# nomis.net
KiCad netlist of a schematic drawn in EAGLE
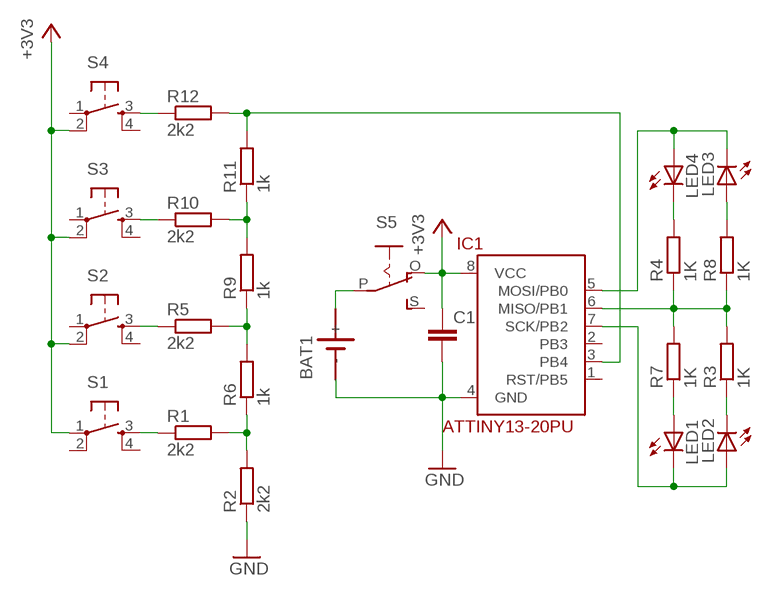
[diagram p0: schematic, sheet 1]

(export (version "E")
  (design (tool "Eeschema 10.0.6"))
  (components
    (comp (ref "BAT1")
      (value "SN2032")
      (footprint "eagle-import:SN2032")
      (libsource (lib "eagle-import") (part "SN2032"))
    )
    (comp (ref "C1")
      (value "C-EU025-025X050")
      (footprint "eagle-import:C025-025X050")
      (libsource (lib "eagle-import") (part "C-EU025-025X050"))
    )
    (comp (ref "IC1")
      (value "ATTINY13-20PU")
      (footprint "eagle-import:DIL08")
      (libsource (lib "eagle-import") (part "ATTINY13-20PU"))
    )
    (comp (ref "LED1")
      (value "LED5MM")
      (footprint "eagle-import:LED5MM")
      (libsource (lib "eagle-import") (part "LED5MM"))
    )
    (comp (ref "LED2")
      (value "LED5MM")
      (footprint "eagle-import:LED5MM")
      (libsource (lib "eagle-import") (part "LED5MM"))
    )
    (comp (ref "LED3")
      (value "LED5MM")
      (footprint "eagle-import:LED5MM")
      (libsource (lib "eagle-import") (part "LED5MM"))
    )
    (comp (ref "LED4")
      (value "LED5MM")
      (footprint "eagle-import:LED5MM")
      (libsource (lib "eagle-import") (part "LED5MM"))
    )
    (comp (ref "R1")
      (value "2k2")
      (footprint "eagle-import:0207_7")
      (libsource (lib "eagle-import") (part "R-EU_0207/7"))
    )
    (comp (ref "R2")
      (value "2k2")
      (footprint "eagle-import:0207_7")
      (libsource (lib "eagle-import") (part "R-EU_0207/7"))
    )
    (comp (ref "R3")
      (value "1K")
      (footprint "eagle-import:0207_7")
      (libsource (lib "eagle-import") (part "R-EU_0207/7"))
    )
    (comp (ref "R4")
      (value "1K")
      (footprint "eagle-import:0207_7")
      (libsource (lib "eagle-import") (part "R-EU_0207/7"))
    )
    (comp (ref "R5")
      (value "2k2")
      (footprint "eagle-import:0207_7")
      (libsource (lib "eagle-import") (part "R-EU_0207/7"))
    )
    (comp (ref "R6")
      (value "1k")
      (footprint "eagle-import:0207_7")
      (libsource (lib "eagle-import") (part "R-EU_0207/7"))
    )
    (comp (ref "R7")
      (value "1K")
      (footprint "eagle-import:0207_7")
      (libsource (lib "eagle-import") (part "R-EU_0207/7"))
    )
    (comp (ref "R8")
      (value "1K")
      (footprint "eagle-import:0207_7")
      (libsource (lib "eagle-import") (part "R-EU_0207/7"))
    )
    (comp (ref "R9")
      (value "1k")
      (footprint "eagle-import:0207_7")
      (libsource (lib "eagle-import") (part "R-EU_0207/7"))
    )
    (comp (ref "R10")
      (value "2k2")
      (footprint "eagle-import:0207_7")
      (libsource (lib "eagle-import") (part "R-EU_0207/7"))
    )
    (comp (ref "R11")
      (value "1k")
      (footprint "eagle-import:0207_7")
      (libsource (lib "eagle-import") (part "R-EU_0207/7"))
    )
    (comp (ref "R12")
      (value "2k2")
      (footprint "eagle-import:0207_7")
      (libsource (lib "eagle-import") (part "R-EU_0207/7"))
    )
    (comp (ref "S1")
      (value "TAC_SWITCHPTH")
      (footprint "eagle-import:TACTILE-PTH")
      (libsource (lib "eagle-import") (part "TAC_SWITCHPTH"))
    )
    (comp (ref "S2")
      (value "TAC_SWITCHPTH")
      (footprint "eagle-import:TACTILE-PTH")
      (libsource (lib "eagle-import") (part "TAC_SWITCHPTH"))
    )
    (comp (ref "S3")
      (value "TAC_SWITCHPTH")
      (footprint "eagle-import:TACTILE-PTH")
      (libsource (lib "eagle-import") (part "TAC_SWITCHPTH"))
    )
    (comp (ref "S4")
      (value "TAC_SWITCHPTH")
      (footprint "eagle-import:TACTILE-PTH")
      (libsource (lib "eagle-import") (part "TAC_SWITCHPTH"))
    )
    (comp (ref "S5")
      (value "EG1218S")
      (footprint "eagle-import:EG1218")
      (libsource (lib "eagle-import") (part "EG1218S"))
    )
  )
  (nets
    (net (code "1") (name "+3V3") (class "Default")
      (node (ref "C1") (pin "1") (pinfunction "1_1") (pintype "passive"))
      (node (ref "IC1") (pin "8") (pinfunction "VCC_8") (pintype "power_in"))
      (node (ref "S1") (pin "1") (pinfunction "1_1") (pintype "passive"))
      (node (ref "S2") (pin "2") (pinfunction "2_2") (pintype "passive"))
      (node (ref "S3") (pin "2") (pinfunction "2_2") (pintype "passive"))
      (node (ref "S4") (pin "2") (pinfunction "2_2") (pintype "passive"))
      (node (ref "S5") (pin "O") (pinfunction "O_O") (pintype "passive"))
    )
    (net (code "2") (name "GND") (class "Default")
      (node (ref "BAT1") (pin "-") (pinfunction "-_-") (pintype "passive"))
      (node (ref "C1") (pin "2") (pinfunction "2_2") (pintype "passive"))
      (node (ref "IC1") (pin "4") (pinfunction "GND_4") (pintype "power_in"))
      (node (ref "R2") (pin "1") (pinfunction "1_1") (pintype "passive"))
    )
    (net (code "3") (name "Net-(BAT1-Pad+)") (class "Default")
      (node (ref "BAT1") (pin "+") (pinfunction "+_+") (pintype "passive"))
      (node (ref "S5") (pin "P") (pinfunction "P_P") (pintype "passive"))
    )
    (net (code "4") (name "Net-(IC1-MISO{slash}PB1)") (class "Default")
      (node (ref "IC1") (pin "6") (pinfunction "MISO/PB1_6") (pintype "bidirectional"))
      (node (ref "R3") (pin "2") (pinfunction "2_2") (pintype "passive"))
      (node (ref "R4") (pin "1") (pinfunction "1_1") (pintype "passive"))
      (node (ref "R7") (pin "2") (pinfunction "2_2") (pintype "passive"))
      (node (ref "R8") (pin "1") (pinfunction "1_1") (pintype "passive"))
    )
    (net (code "5") (name "Net-(IC1-MOSI{slash}PB0)") (class "Default")
      (node (ref "IC1") (pin "5") (pinfunction "MOSI/PB0_5") (pintype "bidirectional"))
      (node (ref "LED3") (pin "K") (pinfunction "C_K") (pintype "passive"))
      (node (ref "LED4") (pin "A") (pinfunction "A_A") (pintype "passive"))
    )
    (net (code "6") (name "Net-(IC1-PB4)") (class "Default")
      (node (ref "IC1") (pin "3") (pinfunction "PB4_3") (pintype "bidirectional"))
      (node (ref "R11") (pin "2") (pinfunction "2_2") (pintype "passive"))
      (node (ref "R12") (pin "2") (pinfunction "2_2") (pintype "passive"))
    )
    (net (code "7") (name "Net-(IC1-SCK{slash}PB2)") (class "Default")
      (node (ref "IC1") (pin "7") (pinfunction "SCK/PB2_7") (pintype "bidirectional"))
      (node (ref "LED1") (pin "K") (pinfunction "C_K") (pintype "passive"))
      (node (ref "LED2") (pin "A") (pinfunction "A_A") (pintype "passive"))
    )
    (net (code "8") (name "Net-(LED1-PadA)") (class "Default")
      (node (ref "LED1") (pin "A") (pinfunction "A_A") (pintype "passive"))
      (node (ref "R7") (pin "1") (pinfunction "1_1") (pintype "passive"))
    )
    (net (code "9") (name "Net-(LED2-C)") (class "Default")
      (node (ref "LED2") (pin "K") (pinfunction "C_K") (pintype "passive"))
      (node (ref "R3") (pin "1") (pinfunction "1_1") (pintype "passive"))
    )
    (net (code "10") (name "Net-(LED3-PadA)") (class "Default")
      (node (ref "LED3") (pin "A") (pinfunction "A_A") (pintype "passive"))
      (node (ref "R8") (pin "2") (pinfunction "2_2") (pintype "passive"))
    )
    (net (code "11") (name "Net-(LED4-C)") (class "Default")
      (node (ref "LED4") (pin "K") (pinfunction "C_K") (pintype "passive"))
      (node (ref "R4") (pin "2") (pinfunction "2_2") (pintype "passive"))
    )
    (net (code "12") (name "Net-(R1-Pad1)") (class "Default")
      (node (ref "R1") (pin "1") (pinfunction "1_1") (pintype "passive"))
      (node (ref "S1") (pin "3") (pinfunction "3_3") (pintype "passive"))
    )
    (net (code "13") (name "Net-(R1-Pad2)") (class "Default")
      (node (ref "R1") (pin "2") (pinfunction "2_2") (pintype "passive"))
      (node (ref "R2") (pin "2") (pinfunction "2_2") (pintype "passive"))
      (node (ref "R6") (pin "1") (pinfunction "1_1") (pintype "passive"))
    )
    (net (code "14") (name "Net-(R5-Pad1)") (class "Default")
      (node (ref "R5") (pin "1") (pinfunction "1_1") (pintype "passive"))
      (node (ref "S2") (pin "3") (pinfunction "3_3") (pintype "passive"))
    )
    (net (code "15") (name "Net-(R5-Pad2)") (class "Default")
      (node (ref "R5") (pin "2") (pinfunction "2_2") (pintype "passive"))
      (node (ref "R6") (pin "2") (pinfunction "2_2") (pintype "passive"))
      (node (ref "R9") (pin "1") (pinfunction "1_1") (pintype "passive"))
    )
    (net (code "16") (name "Net-(R10-Pad1)") (class "Default")
      (node (ref "R10") (pin "1") (pinfunction "1_1") (pintype "passive"))
      (node (ref "S3") (pin "3") (pinfunction "3_3") (pintype "passive"))
    )
    (net (code "17") (name "Net-(R10-Pad2)") (class "Default")
      (node (ref "R10") (pin "2") (pinfunction "2_2") (pintype "passive"))
      (node (ref "R11") (pin "1") (pinfunction "1_1") (pintype "passive"))
      (node (ref "R9") (pin "2") (pinfunction "2_2") (pintype "passive"))
    )
    (net (code "18") (name "Net-(R12-Pad1)") (class "Default")
      (node (ref "R12") (pin "1") (pinfunction "1_1") (pintype "passive"))
      (node (ref "S4") (pin "3") (pinfunction "3_3") (pintype "passive"))
    )
    (net (code "19") (name "unconnected-(IC1-PB3-Pad2)") (class "Default")
      (node (ref "IC1") (pin "2") (pinfunction "PB3_2") (pintype "bidirectional"))
    )
    (net (code "20") (name "unconnected-(IC1-RST{slash}PB5-Pad1)") (class "Default")
      (node (ref "IC1") (pin "1") (pinfunction "RST/PB5_1") (pintype "bidirectional"))
    )
    (net (code "21") (name "unconnected-(S1-Pad2)") (class "Default")
      (node (ref "S1") (pin "2") (pinfunction "2_2") (pintype "passive"))
    )
    (net (code "22") (name "unconnected-(S1-Pad4)") (class "Default")
      (node (ref "S1") (pin "4") (pinfunction "4_4") (pintype "passive"))
    )
    (net (code "23") (name "unconnected-(S2-Pad1)") (class "Default")
      (node (ref "S2") (pin "1") (pinfunction "1_1") (pintype "passive"))
    )
    (net (code "24") (name "unconnected-(S2-Pad4)") (class "Default")
      (node (ref "S2") (pin "4") (pinfunction "4_4") (pintype "passive"))
    )
    (net (code "25") (name "unconnected-(S3-Pad1)") (class "Default")
      (node (ref "S3") (pin "1") (pinfunction "1_1") (pintype "passive"))
    )
    (net (code "26") (name "unconnected-(S3-Pad4)") (class "Default")
      (node (ref "S3") (pin "4") (pinfunction "4_4") (pintype "passive"))
    )
    (net (code "27") (name "unconnected-(S4-Pad1)") (class "Default")
      (node (ref "S4") (pin "1") (pinfunction "1_1") (pintype "passive"))
    )
    (net (code "28") (name "unconnected-(S4-Pad4)") (class "Default")
      (node (ref "S4") (pin "4") (pinfunction "4_4") (pintype "passive"))
    )
    (net (code "29") (name "unconnected-(S5-PadS)") (class "Default")
      (node (ref "S5") (pin "S") (pinfunction "S_S") (pintype "passive"))
    )
  )
)
